# SSR_Switch.net
KiCad netlist of a schematic drawn in EasyEDA Pro
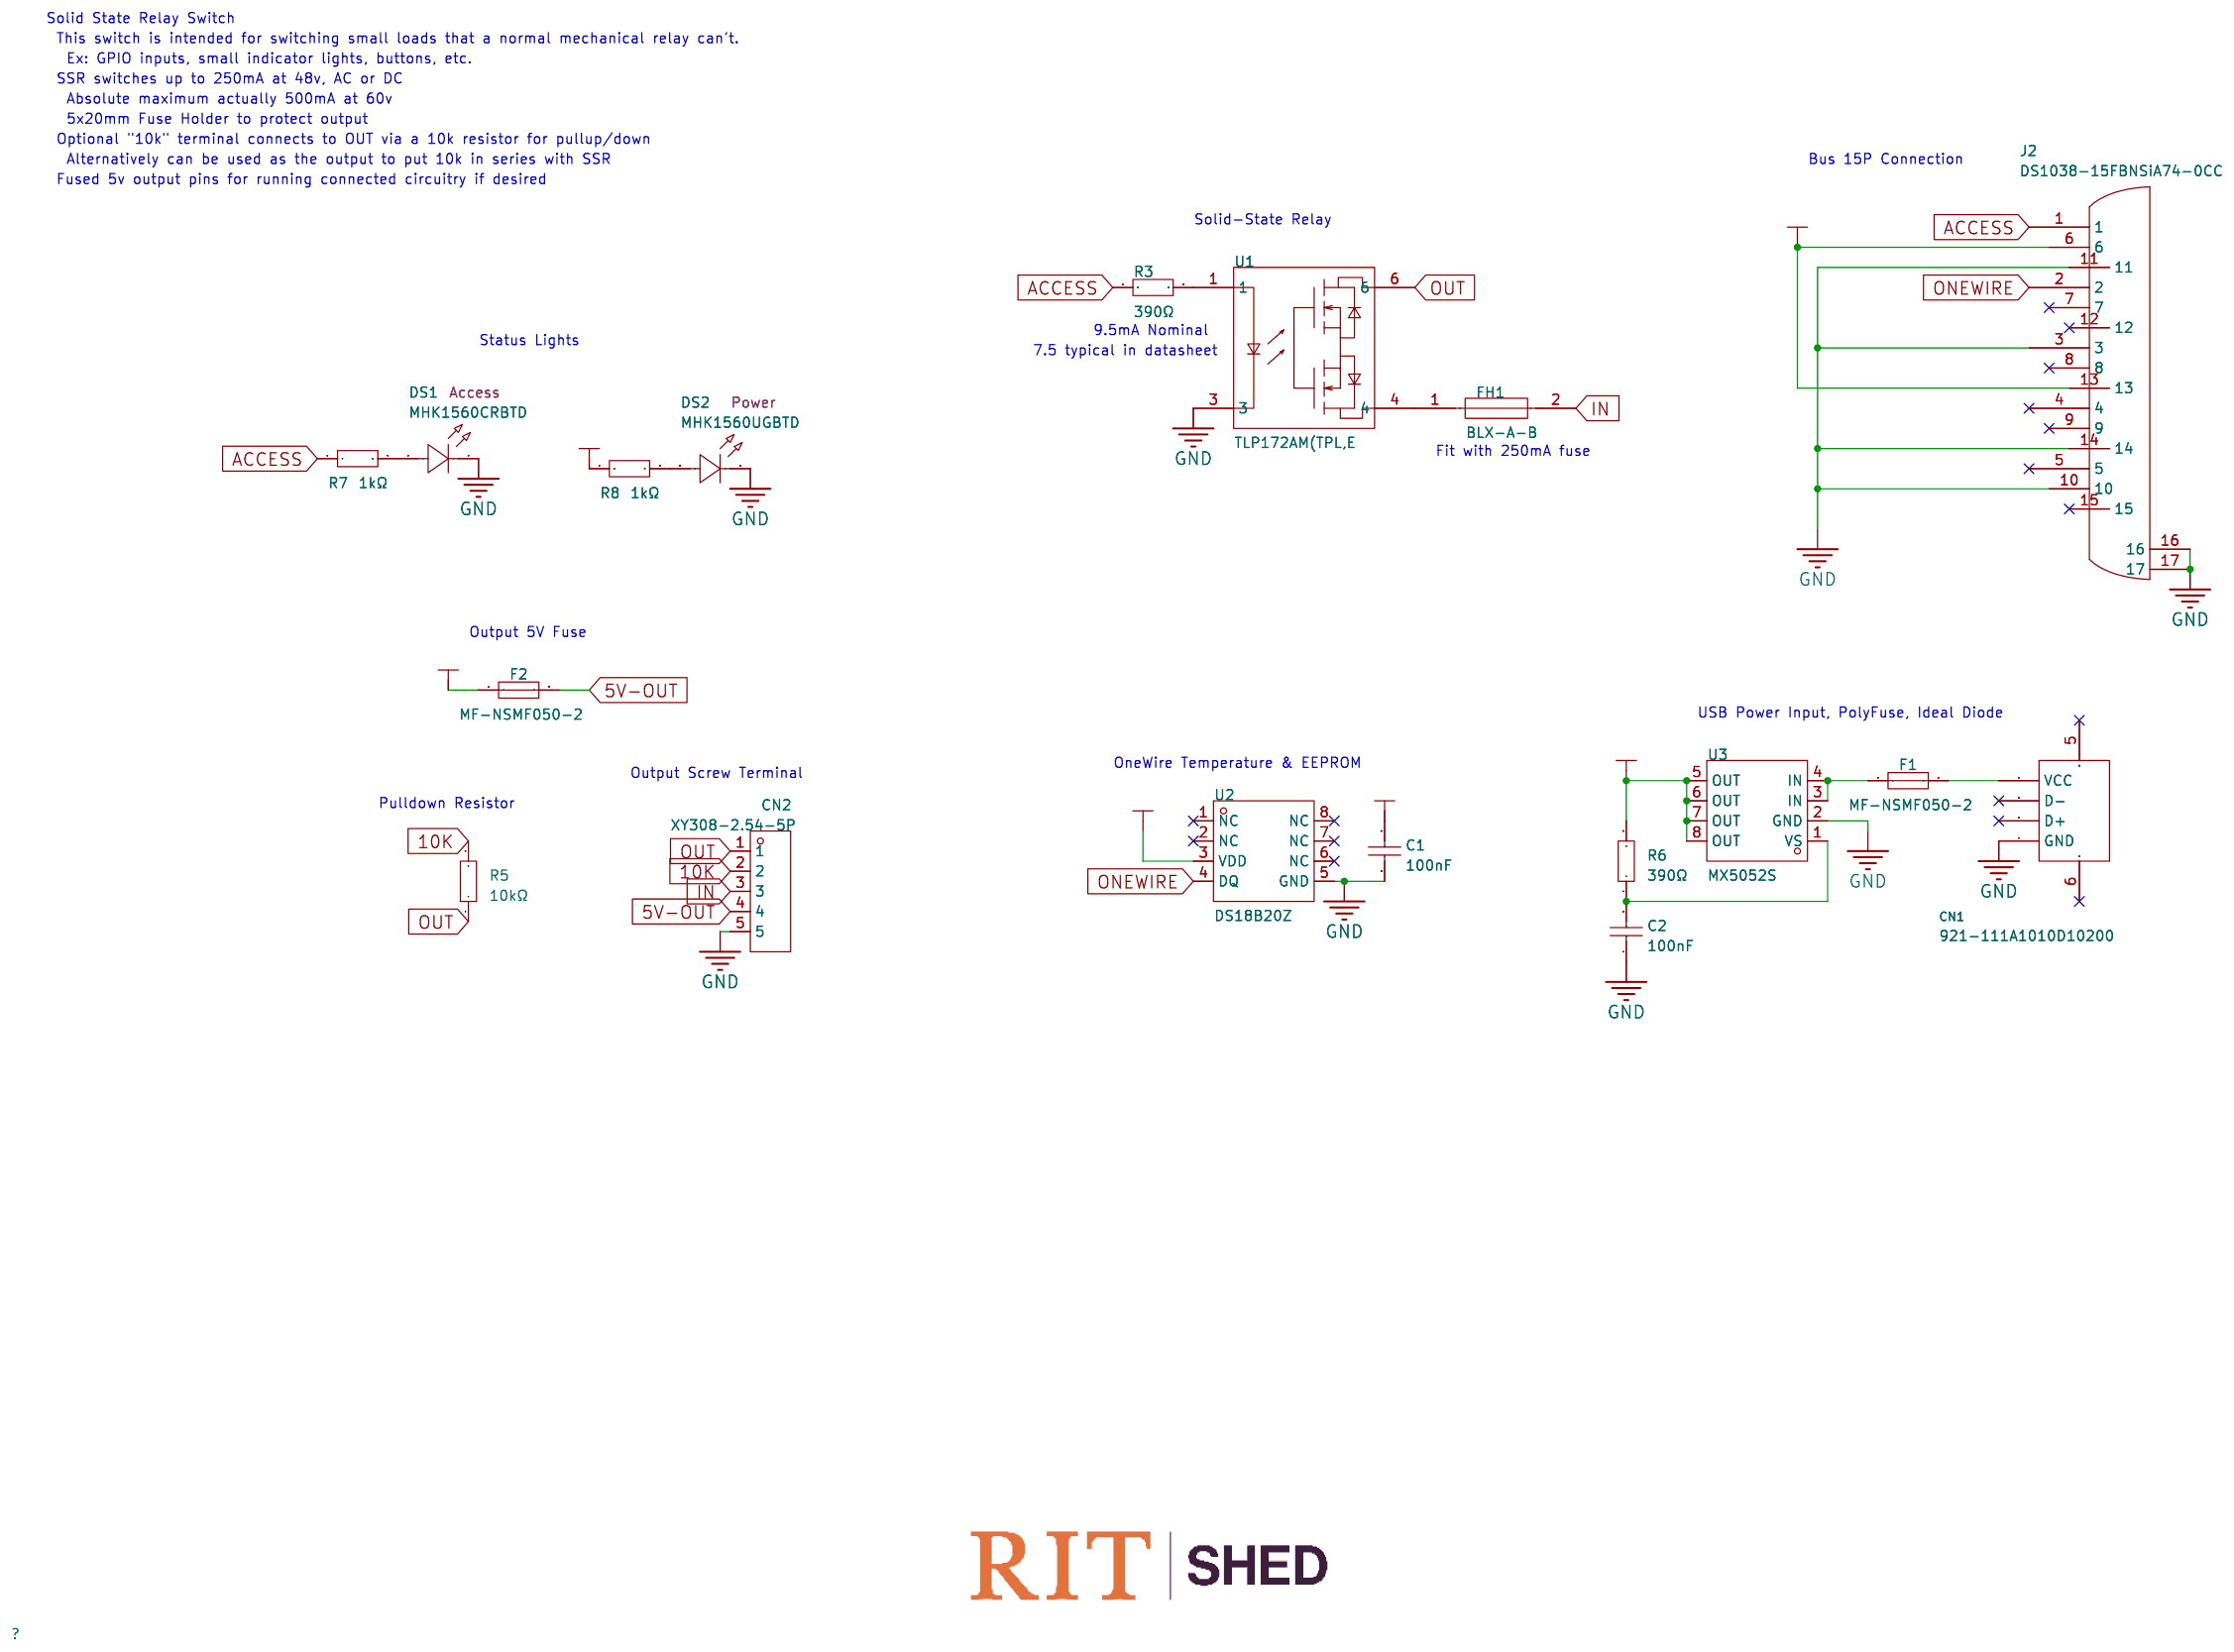
[diagram p0: schematic sheet]

(export (version "E")
  (design (tool "Eeschema 10.0.6"))
  (components
    (comp (ref "C1")
      (value "100nF")
      (footprint "easyedapro:C0805")
      (description "Capacitance:100nF Tolerance:±10% Tolerance:±10% Voltage Rating:100V Temperature Coefficient:X7R")
      (fields
        (field (name "Manufacturer Part") "CL21B104KCFNNNE")
        (field (name "Manufacturer") "SAMSUNG(三星)")
      )
      (libsource (lib "easyedapro") (part "CL21B104KCFNNNE"))
    )
    (comp (ref "C2")
      (value "100nF")
      (footprint "easyedapro:C0805")
      (description "Capacitance:100nF Tolerance:±10% Tolerance:±10% Voltage Rating:100V Temperature Coefficient:X7R")
      (fields
        (field (name "Manufacturer Part") "CL21B104KCFNNNE")
        (field (name "Manufacturer") "SAMSUNG(三星)")
      )
      (libsource (lib "easyedapro") (part "CL21B104KCFNNNE"))
    )
    (comp (ref "CN1")
      (value "921-111A1010D10200")
      (footprint "easyedapro:USB-B_TH_USB-B-FEMALE-90")
      (fields (field (name "Manufacturer") "精拓金"))
      (libsource (lib "easyedapro") (part "USB-B-Female-90"))
    )
    (comp (ref "CN2")
      (value "XY308-2.54-5P")
      (footprint "easyedapro:CONN-TH_XY308-2.54-5P")
      (fields (field (name "Manufacturer") "XINLAIYA(新莱亚)"))
      (libsource (lib "easyedapro") (part "XY308-2.54-5P"))
    )
    (comp (ref "DS1")
      (value "MHK1560CRBTD")
      (footprint "easyedapro:LED-TH_MHK1560UGBTD")
      (fields (field (name "Manufacturer") "MEIHUA(美华)") (field (name "Note") "Access"))
      (libsource (lib "easyedapro") (part "MHK1560CGBTD"))
    )
    (comp (ref "DS2")
      (value "MHK1560UGBTD")
      (footprint "easyedapro:LED-TH_MHK1560UGBTD")
      (fields (field (name "Manufacturer") "MEIHUA(美华)") (field (name "Note") "Power"))
      (libsource (lib "easyedapro") (part "MHK1560UGBTD"))
    )
    (comp (ref "F1")
      (value "MF-NSMF050-2")
      (footprint "easyedapro:F1206")
      (fields (field (name "Manufacturer") "BOURNS"))
      (libsource (lib "easyedapro") (part "MF-NSMF050-2"))
    )
    (comp (ref "F2")
      (value "MF-NSMF050-2")
      (footprint "easyedapro:F1206")
      (fields (field (name "Manufacturer") "BOURNS"))
      (libsource (lib "easyedapro") (part "MF-NSMF050-2"))
    )
    (comp (ref "FH1")
      (value "BLX-A-B")
      (footprint "easyedapro:FUSE-TH_BLX-A-B")
      (fields (field (name "Manufacturer") "XFCN(兴飞)"))
      (libsource (lib "easyedapro") (part "BLX-A-B"))
    )
    (comp (ref "J2")
      (value "DS1038-15FBNSiA74-0CC")
      (footprint "easyedapro:DSUB-TH_DS1038-15FBNSIA74-0CC")
      (fields (field (name "Manufacturer") "CONNFLY"))
      (libsource (lib "easyedapro") (part "DS1038-15FBNSIA74-0CC"))
    )
    (comp (ref "R3")
      (value "390Ω")
      (footprint "easyedapro:R0805")
      (fields
        (field (name "Manufacturer Part") "0805W8F3900T5E")
        (field (name "Manufacturer") "UNI-ROYAL(厚声)")
      )
      (libsource (lib "easyedapro") (part "0805W8F3900T5E"))
    )
    (comp (ref "R5")
      (value "10kΩ")
      (footprint "easyedapro:R0805")
      (fields
        (field (name "Manufacturer Part") "0805W8F1002T5E")
        (field (name "Manufacturer") "UNI-ROYAL(厚声)")
      )
      (libsource (lib "easyedapro") (part "0805W8F1002T5E"))
    )
    (comp (ref "R6")
      (value "390Ω")
      (footprint "easyedapro:R0805")
      (fields
        (field (name "Manufacturer Part") "0805W8F3900T5E")
        (field (name "Manufacturer") "UNI-ROYAL(厚声)")
      )
      (libsource (lib "easyedapro") (part "0805W8F3900T5E"))
    )
    (comp (ref "R7")
      (value "1kΩ")
      (footprint "easyedapro:R0805")
      (fields
        (field (name "Manufacturer Part") "0805W8F1001T5E")
        (field (name "Manufacturer") "UNI-ROYAL(厚声)")
      )
      (libsource (lib "easyedapro") (part "0805W8F1001T5E"))
    )
    (comp (ref "R8")
      (value "1kΩ")
      (footprint "easyedapro:R0805")
      (fields
        (field (name "Manufacturer Part") "0805W8F1001T5E")
        (field (name "Manufacturer") "UNI-ROYAL(厚声)")
      )
      (libsource (lib "easyedapro") (part "0805W8F1001T5E"))
    )
    (comp (ref "U1")
      (value "TLP172AM(TPL,E")
      (footprint "easyedapro:SOP-6_4P-L3.7-W4.6-P2.54-LS7.0-BL")
      (fields (field (name "Manufacturer") "TOSHIBA(东芝)"))
      (libsource (lib "easyedapro") (part "TLP172AM(TPL,E"))
    )
    (comp (ref "U2")
      (value "DS18B20Z")
      (footprint "easyedapro:SOP-8_L4.9-W3.9-P1.27-LS6.0-BL")
      (description "Resolution:±0.4°C Resolution:±0.4°C Supply Voltage:2.5V~5.5V Supply Voltage:2.5V~5.5V")
      (fields (field (name "Manufacturer") "UMW(友台半导体)"))
      (libsource (lib "easyedapro") (part "DS18B20Z"))
    )
    (comp (ref "U3")
      (value "MX5052S")
      (footprint "easyedapro:SOP-8_L4.9-W3.9-P1.27-LS6.0-BL")
      (fields (field (name "Manufacturer") "Wuxi Maxinmicro(无锡明芯微)"))
      (libsource (lib "easyedapro") (part "MX5052S"))
    )
  )
  (nets
    (net (code "1") (name "+5V-BUS") (class "Default")
      (node (ref "C1") (pin "2") (pinfunction "2_2") (pintype "input"))
      (node (ref "F2") (pin "1") (pinfunction "1_1") (pintype "unspecified"))
      (node (ref "J2") (pin "13") (pinfunction "13_13") (pintype "unspecified"))
      (node (ref "J2") (pin "6") (pinfunction "6_6") (pintype "unspecified"))
      (node (ref "R6") (pin "2") (pinfunction "2_2") (pintype "input"))
      (node (ref "R8") (pin "1") (pinfunction "1_1") (pintype "input"))
      (node (ref "U2") (pin "3") (pinfunction "VDD_3") (pintype "unspecified"))
      (node (ref "U3") (pin "5") (pinfunction "OUT_5") (pintype "unspecified"))
      (node (ref "U3") (pin "6") (pinfunction "OUT_6") (pintype "unspecified"))
      (node (ref "U3") (pin "7") (pinfunction "OUT_7") (pintype "unspecified"))
      (node (ref "U3") (pin "8") (pinfunction "OUT_8") (pintype "unspecified"))
    )
    (net (code "2") (name "5V-OUT") (class "Default")
      (node (ref "CN2") (pin "4") (pinfunction "4_4") (pintype "unspecified"))
      (node (ref "F2") (pin "2") (pinfunction "2_2") (pintype "unspecified"))
    )
    (net (code "3") (name "10K") (class "Default")
      (node (ref "CN2") (pin "2") (pinfunction "2_2") (pintype "unspecified"))
      (node (ref "R5") (pin "2") (pinfunction "2_2") (pintype "input"))
    )
    (net (code "4") (name "ACCESS") (class "Default")
      (node (ref "J2") (pin "1") (pinfunction "1_1") (pintype "unspecified"))
      (node (ref "R3") (pin "1") (pinfunction "1_1") (pintype "input"))
      (node (ref "R7") (pin "1") (pinfunction "1_1") (pintype "input"))
    )
    (net (code "5") (name "GND") (class "Default")
      (node (ref "C1") (pin "1") (pinfunction "1_1") (pintype "input"))
      (node (ref "C2") (pin "1") (pinfunction "1_1") (pintype "input"))
      (node (ref "CN1") (pin "4") (pinfunction "GND_4") (pintype "input"))
      (node (ref "CN2") (pin "5") (pinfunction "5_5") (pintype "unspecified"))
      (node (ref "DS1") (pin "1") (pinfunction "K_1") (pintype "unspecified"))
      (node (ref "DS2") (pin "1") (pinfunction "K_1") (pintype "unspecified"))
      (node (ref "J2") (pin "10") (pinfunction "10_10") (pintype "unspecified"))
      (node (ref "J2") (pin "11") (pinfunction "11_11") (pintype "unspecified"))
      (node (ref "J2") (pin "14") (pinfunction "14_14") (pintype "unspecified"))
      (node (ref "J2") (pin "16") (pinfunction "16_16") (pintype "unspecified"))
      (node (ref "J2") (pin "17") (pinfunction "17_17") (pintype "unspecified"))
      (node (ref "J2") (pin "3") (pinfunction "3_3") (pintype "unspecified"))
      (node (ref "U1") (pin "3") (pinfunction "3_3") (pintype "unspecified"))
      (node (ref "U2") (pin "5") (pinfunction "GND_5") (pintype "unspecified"))
      (node (ref "U3") (pin "2") (pinfunction "GND_2") (pintype "unspecified"))
    )
    (net (code "6") (name "IN") (class "Default")
      (node (ref "CN2") (pin "3") (pinfunction "3_3") (pintype "unspecified"))
      (node (ref "FH1") (pin "2") (pinfunction "2_2") (pintype "unspecified"))
    )
    (net (code "7") (name "Net-(CN1-VCC)") (class "Default")
      (node (ref "CN1") (pin "1") (pinfunction "VCC_1") (pintype "input"))
      (node (ref "F1") (pin "2") (pinfunction "2_2") (pintype "unspecified"))
    )
    (net (code "8") (name "Net-(DS1-A)") (class "Default")
      (node (ref "DS1") (pin "2") (pinfunction "A_2") (pintype "unspecified"))
      (node (ref "R7") (pin "2") (pinfunction "2_2") (pintype "input"))
    )
    (net (code "9") (name "Net-(DS2-A)") (class "Default")
      (node (ref "DS2") (pin "2") (pinfunction "A_2") (pintype "unspecified"))
      (node (ref "R8") (pin "2") (pinfunction "2_2") (pintype "input"))
    )
    (net (code "10") (name "Net-(F1-Pad1)") (class "Default")
      (node (ref "F1") (pin "1") (pinfunction "1_1") (pintype "unspecified"))
      (node (ref "U3") (pin "3") (pinfunction "IN_3") (pintype "unspecified"))
      (node (ref "U3") (pin "4") (pinfunction "IN_4") (pintype "unspecified"))
    )
    (net (code "11") (name "Net-(FH1-Pad1)") (class "Default")
      (node (ref "FH1") (pin "1") (pinfunction "1_1") (pintype "unspecified"))
      (node (ref "U1") (pin "4") (pinfunction "4_4") (pintype "unspecified"))
    )
    (net (code "12") (name "Net-(R3-Pad2)") (class "Default")
      (node (ref "R3") (pin "2") (pinfunction "2_2") (pintype "input"))
      (node (ref "U1") (pin "1") (pinfunction "1_1") (pintype "unspecified"))
    )
    (net (code "13") (name "Net-(U3-VS)") (class "Default")
      (node (ref "C2") (pin "2") (pinfunction "2_2") (pintype "input"))
      (node (ref "R6") (pin "1") (pinfunction "1_1") (pintype "input"))
      (node (ref "U3") (pin "1") (pinfunction "VS_1") (pintype "unspecified"))
    )
    (net (code "14") (name "ONEWIRE") (class "Default")
      (node (ref "J2") (pin "2") (pinfunction "2_2") (pintype "unspecified"))
      (node (ref "U2") (pin "4") (pinfunction "DQ_4") (pintype "unspecified"))
    )
    (net (code "15") (name "OUT") (class "Default")
      (node (ref "CN2") (pin "1") (pinfunction "1_1") (pintype "unspecified"))
      (node (ref "R5") (pin "1") (pinfunction "1_1") (pintype "input"))
      (node (ref "U1") (pin "6") (pinfunction "6_6") (pintype "unspecified"))
    )
    (net (code "16") (name "unconnected-(CN1-D+-Pad3)") (class "Default")
      (node (ref "CN1") (pin "3") (pinfunction "D+_3") (pintype "input+no_connect"))
    )
    (net (code "17") (name "unconnected-(CN1-D--Pad2)") (class "Default")
      (node (ref "CN1") (pin "2") (pinfunction "D-_2") (pintype "input+no_connect"))
    )
    (net (code "18") (name "unconnected-(CN1-SH1-Pad5)") (class "Default")
      (node (ref "CN1") (pin "5") (pinfunction "SH1_5") (pintype "input+no_connect"))
    )
    (net (code "19") (name "unconnected-(CN1-SH2-Pad6)") (class "Default")
      (node (ref "CN1") (pin "6") (pinfunction "SH2_6") (pintype "input+no_connect"))
    )
    (net (code "20") (name "unconnected-(J2-Pad4)") (class "Default")
      (node (ref "J2") (pin "4") (pinfunction "4_4") (pintype "unspecified+no_connect"))
    )
    (net (code "21") (name "unconnected-(J2-Pad5)") (class "Default")
      (node (ref "J2") (pin "5") (pinfunction "5_5") (pintype "unspecified+no_connect"))
    )
    (net (code "22") (name "unconnected-(J2-Pad7)") (class "Default")
      (node (ref "J2") (pin "7") (pinfunction "7_7") (pintype "unspecified+no_connect"))
    )
    (net (code "23") (name "unconnected-(J2-Pad8)") (class "Default")
      (node (ref "J2") (pin "8") (pinfunction "8_8") (pintype "unspecified+no_connect"))
    )
    (net (code "24") (name "unconnected-(J2-Pad9)") (class "Default")
      (node (ref "J2") (pin "9") (pinfunction "9_9") (pintype "unspecified+no_connect"))
    )
    (net (code "25") (name "unconnected-(J2-Pad12)") (class "Default")
      (node (ref "J2") (pin "12") (pinfunction "12_12") (pintype "unspecified+no_connect"))
    )
    (net (code "26") (name "unconnected-(J2-Pad15)") (class "Default")
      (node (ref "J2") (pin "15") (pinfunction "15_15") (pintype "unspecified+no_connect"))
    )
    (net (code "27") (name "unconnected-(U2-NC-Pad1)") (class "Default")
      (node (ref "U2") (pin "1") (pinfunction "NC_1") (pintype "unspecified+no_connect"))
    )
    (net (code "28") (name "unconnected-(U2-NC-Pad2)") (class "Default")
      (node (ref "U2") (pin "2") (pinfunction "NC_2") (pintype "unspecified+no_connect"))
    )
    (net (code "29") (name "unconnected-(U2-NC-Pad6)") (class "Default")
      (node (ref "U2") (pin "6") (pinfunction "NC_6") (pintype "unspecified+no_connect"))
    )
    (net (code "30") (name "unconnected-(U2-NC-Pad7)") (class "Default")
      (node (ref "U2") (pin "7") (pinfunction "NC_7") (pintype "unspecified+no_connect"))
    )
    (net (code "31") (name "unconnected-(U2-NC-Pad8)") (class "Default")
      (node (ref "U2") (pin "8") (pinfunction "NC_8") (pintype "unspecified+no_connect"))
    )
  )
)
